# OSSC_HDMI_Audio_v1_5_A3.net
KiCad netlist of a schematic drawn in EAGLE
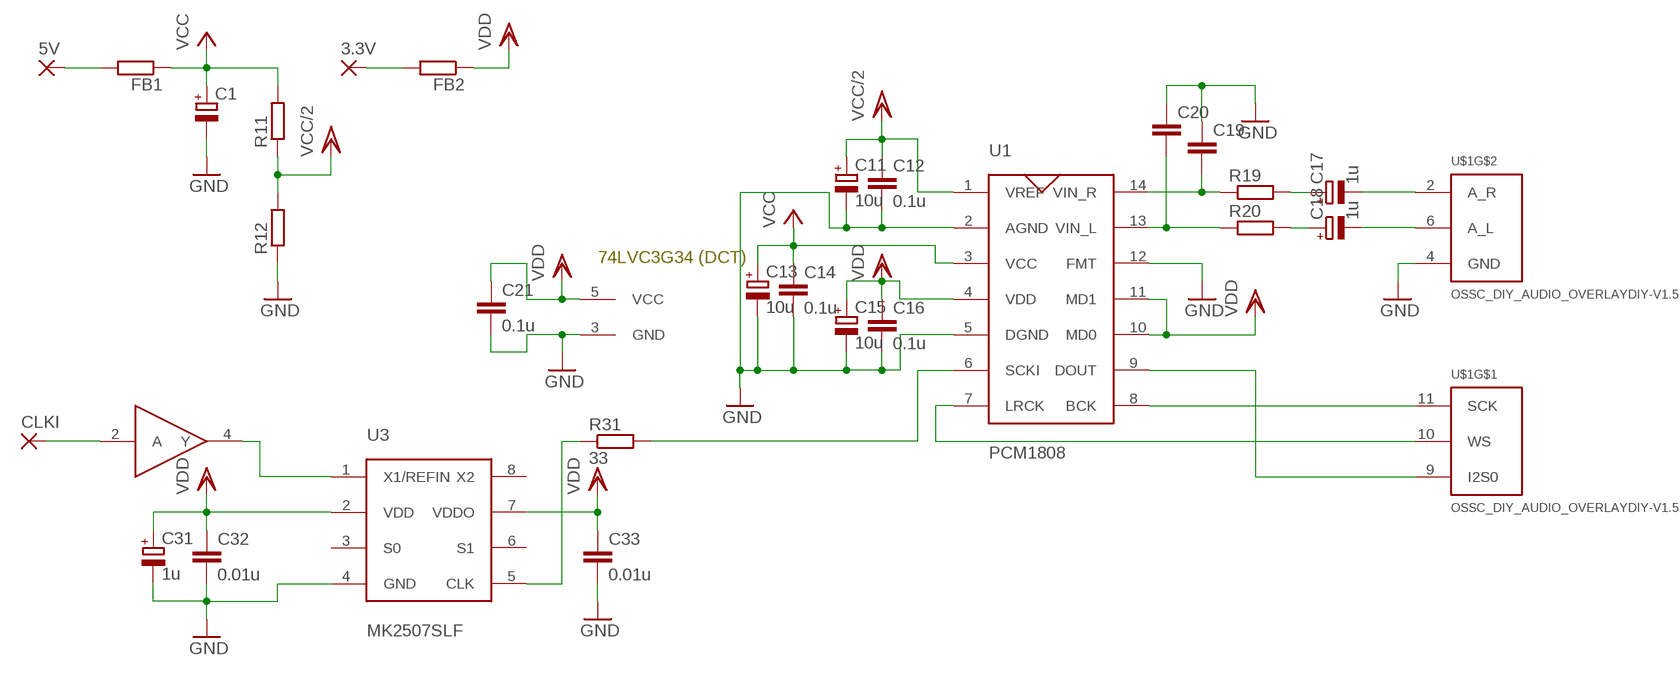
[diagram p0: schematic, sheet 1]

(export (version "E")
  (design (tool "Eeschema 10.0.6"))
  (components
    (comp (ref "3.3V")
      (value "SMD2")
      (footprint "eagle-import:SMD1,27-2,54")
      (libsource (lib "eagle-import") (part "SMD2"))
    )
    (comp (ref "5V")
      (value "SMD2")
      (footprint "eagle-import:SMD1,27-2,54")
      (libsource (lib "eagle-import") (part "SMD2"))
    )
    (comp (ref "C1")
      (value "CPOL-EUSMCC")
      (footprint "eagle-import:SMC_C")
      (libsource (lib "eagle-import") (part "CPOL-EUSMCC"))
    )
    (comp (ref "C11")
      (value "10u")
      (footprint "eagle-import:SMC_A")
      (libsource (lib "eagle-import") (part "CPOL-EUSMCA"))
    )
    (comp (ref "C12")
      (value "0.1u")
      (footprint "eagle-import:C0603")
      (libsource (lib "eagle-import") (part "C-EUC0603"))
    )
    (comp (ref "C13")
      (value "10u")
      (footprint "eagle-import:SMC_A")
      (libsource (lib "eagle-import") (part "CPOL-EUSMCA"))
    )
    (comp (ref "C14")
      (value "0.1u")
      (footprint "eagle-import:C0603")
      (libsource (lib "eagle-import") (part "C-EUC0603"))
    )
    (comp (ref "C15")
      (value "10u")
      (footprint "eagle-import:SMC_A")
      (libsource (lib "eagle-import") (part "CPOL-EUSMCA"))
    )
    (comp (ref "C16")
      (value "0.1u")
      (footprint "eagle-import:C0603")
      (libsource (lib "eagle-import") (part "C-EUC0603"))
    )
    (comp (ref "C17")
      (value "1u")
      (footprint "eagle-import:SMC_A")
      (libsource (lib "eagle-import") (part "CPOL-EUSMCA"))
    )
    (comp (ref "C18")
      (value "1u")
      (footprint "eagle-import:SMC_A")
      (libsource (lib "eagle-import") (part "CPOL-EUSMCA"))
    )
    (comp (ref "C19")
      (value "C-EUC0603")
      (footprint "eagle-import:C0603")
      (libsource (lib "eagle-import") (part "C-EUC0603"))
    )
    (comp (ref "C20")
      (value "C-EUC0603")
      (footprint "eagle-import:C0603")
      (libsource (lib "eagle-import") (part "C-EUC0603"))
    )
    (comp (ref "C21")
      (value "0.1u")
      (footprint "eagle-import:C0603")
      (libsource (lib "eagle-import") (part "C-EUC0603"))
    )
    (comp (ref "C31")
      (value "1u")
      (footprint "eagle-import:SMC_A")
      (libsource (lib "eagle-import") (part "CPOL-EUSMCA"))
    )
    (comp (ref "C32")
      (value "0.01u")
      (footprint "eagle-import:C0603")
      (libsource (lib "eagle-import") (part "C-EUC0603"))
    )
    (comp (ref "C33")
      (value "0.01u")
      (footprint "eagle-import:C0603")
      (libsource (lib "eagle-import") (part "C-EUC0603"))
    )
    (comp (ref "CLKI")
      (value "SMD2")
      (footprint "eagle-import:SMD1,27-2,54")
      (libsource (lib "eagle-import") (part "SMD2"))
    )
    (comp (ref "FB1")
      (value "R-EU_R0603")
      (footprint "eagle-import:R0603")
      (libsource (lib "eagle-import") (part "R-EU_R0603"))
    )
    (comp (ref "FB2")
      (value "R-EU_R0603")
      (footprint "eagle-import:R0603")
      (libsource (lib "eagle-import") (part "R-EU_R0603"))
    )
    (comp (ref "R11")
      (value "R-EU_R0603")
      (footprint "eagle-import:R0603")
      (libsource (lib "eagle-import") (part "R-EU_R0603"))
    )
    (comp (ref "R12")
      (value "R-EU_R0603")
      (footprint "eagle-import:R0603")
      (libsource (lib "eagle-import") (part "R-EU_R0603"))
    )
    (comp (ref "R19")
      (value "R-EU_R0603")
      (footprint "eagle-import:R0603")
      (libsource (lib "eagle-import") (part "R-EU_R0603"))
    )
    (comp (ref "R20")
      (value "R-EU_R0603")
      (footprint "eagle-import:R0603")
      (libsource (lib "eagle-import") (part "R-EU_R0603"))
    )
    (comp (ref "R31")
      (value "33")
      (footprint "eagle-import:R0603")
      (libsource (lib "eagle-import") (part "R-EU_R0603"))
    )
    (comp (ref "U$1")
      (value "OSSC_DIY_AUDIO_OVERLAYDIY-V1.5")
      (footprint "eagle-import:OSSC_OVERLAY_V1.5")
      (libsource (lib "eagle-import") (part "OSSC_DIY_AUDIO_OVERLAYDIY-V1.5"))
    )
    (comp (ref "U1")
      (value "PCM1808")
      (footprint "eagle-import:PCM1808")
      (libsource (lib "eagle-import") (part "PCM1808"))
    )
    (comp (ref "U2")
      (value "74LVC1G34")
      (footprint "eagle-import:74LVC1G34DCK")
      (libsource (lib "eagle-import") (part "74LVC1G34"))
    )
    (comp (ref "U3")
      (value "MK2507SLF")
      (footprint "eagle-import:SOIC8")
      (libsource (lib "eagle-import") (part "MK2507SLF"))
    )
  )
  (nets
    (net (code "1") (name "GND") (class "Default")
      (node (ref "C1") (pin "-") (pinfunction "-_-") (pintype "passive"))
      (node (ref "C11") (pin "-") (pinfunction "-_-") (pintype "passive"))
      (node (ref "C12") (pin "2") (pinfunction "2_2") (pintype "passive"))
      (node (ref "C13") (pin "-") (pinfunction "-_-") (pintype "passive"))
      (node (ref "C14") (pin "2") (pinfunction "2_2") (pintype "passive"))
      (node (ref "C15") (pin "-") (pinfunction "-_-") (pintype "passive"))
      (node (ref "C16") (pin "2") (pinfunction "2_2") (pintype "passive"))
      (node (ref "C19") (pin "1") (pinfunction "1_1") (pintype "passive"))
      (node (ref "C20") (pin "1") (pinfunction "1_1") (pintype "passive"))
      (node (ref "C21") (pin "2") (pinfunction "2_2") (pintype "passive"))
      (node (ref "C31") (pin "-") (pinfunction "-_-") (pintype "passive"))
      (node (ref "C32") (pin "2") (pinfunction "2_2") (pintype "passive"))
      (node (ref "C33") (pin "2") (pinfunction "2_2") (pintype "passive"))
      (node (ref "R12") (pin "1") (pinfunction "1_1") (pintype "passive"))
      (node (ref "U$1") (pin "4") (pinfunction "GND_4") (pintype "bidirectional"))
      (node (ref "U1") (pin "12") (pinfunction "FMT_12") (pintype "bidirectional"))
      (node (ref "U1") (pin "2") (pinfunction "AGND_2") (pintype "bidirectional"))
      (node (ref "U1") (pin "5") (pinfunction "DGND_5") (pintype "bidirectional"))
      (node (ref "U2") (pin "3") (pinfunction "GND_3") (pintype "bidirectional"))
      (node (ref "U3") (pin "4") (pinfunction "GND_4") (pintype "bidirectional"))
    )
    (net (code "2") (name "Net-(3.3V-P)") (class "Default")
      (node (ref "3.3V") (pin "1") (pinfunction "P_1") (pintype "passive"))
      (node (ref "FB2") (pin "2") (pinfunction "2_2") (pintype "passive"))
    )
    (net (code "3") (name "Net-(5V-P)") (class "Default")
      (node (ref "5V") (pin "1") (pinfunction "P_1") (pintype "passive"))
      (node (ref "FB1") (pin "2") (pinfunction "2_2") (pintype "passive"))
    )
    (net (code "4") (name "Net-(C17-Pad+)") (class "Default")
      (node (ref "C17") (pin "+") (pinfunction "+_+") (pintype "passive"))
      (node (ref "R19") (pin "2") (pinfunction "2_2") (pintype "passive"))
    )
    (net (code "5") (name "Net-(C18-Pad+)") (class "Default")
      (node (ref "C18") (pin "+") (pinfunction "+_+") (pintype "passive"))
      (node (ref "R20") (pin "2") (pinfunction "2_2") (pintype "passive"))
    )
    (net (code "6") (name "Net-(CLKI-P)") (class "Default")
      (node (ref "CLKI") (pin "1") (pinfunction "P_1") (pintype "passive"))
      (node (ref "U2") (pin "2") (pinfunction "A_2") (pintype "bidirectional"))
    )
    (net (code "7") (name "Net-(U$1A-I2S0)") (class "Default")
      (node (ref "U$1") (pin "9") (pinfunction "I2S0_9") (pintype "bidirectional"))
      (node (ref "U1") (pin "9") (pinfunction "DOUT_9") (pintype "bidirectional"))
    )
    (net (code "8") (name "Net-(U$1A-SCK)") (class "Default")
      (node (ref "U$1") (pin "11") (pinfunction "SCK_11") (pintype "bidirectional"))
      (node (ref "U1") (pin "8") (pinfunction "BCK_8") (pintype "bidirectional"))
    )
    (net (code "9") (name "Net-(U$1A-WS)") (class "Default")
      (node (ref "U$1") (pin "10") (pinfunction "WS_10") (pintype "bidirectional"))
      (node (ref "U1") (pin "7") (pinfunction "LRCK_7") (pintype "bidirectional"))
    )
    (net (code "10") (name "Net-(U$1B-A_L)") (class "Default")
      (node (ref "C18") (pin "-") (pinfunction "-_-") (pintype "passive"))
      (node (ref "U$1") (pin "6") (pinfunction "A_L_6") (pintype "bidirectional"))
    )
    (net (code "11") (name "Net-(U$1B-A_R)") (class "Default")
      (node (ref "C17") (pin "-") (pinfunction "-_-") (pintype "passive"))
      (node (ref "U$1") (pin "2") (pinfunction "A_R_2") (pintype "bidirectional"))
    )
    (net (code "12") (name "Net-(U1-SCKI)") (class "Default")
      (node (ref "R31") (pin "2") (pinfunction "2_2") (pintype "passive"))
      (node (ref "U1") (pin "6") (pinfunction "SCKI_6") (pintype "bidirectional"))
    )
    (net (code "13") (name "Net-(U1-VIN_L)") (class "Default")
      (node (ref "C20") (pin "2") (pinfunction "2_2") (pintype "passive"))
      (node (ref "R20") (pin "1") (pinfunction "1_1") (pintype "passive"))
      (node (ref "U1") (pin "13") (pinfunction "VIN_L_13") (pintype "bidirectional"))
    )
    (net (code "14") (name "Net-(U1-VIN_R)") (class "Default")
      (node (ref "C19") (pin "2") (pinfunction "2_2") (pintype "passive"))
      (node (ref "R19") (pin "1") (pinfunction "1_1") (pintype "passive"))
      (node (ref "U1") (pin "14") (pinfunction "VIN_R_14") (pintype "bidirectional"))
    )
    (net (code "15") (name "Net-(U2A-Y)") (class "Default")
      (node (ref "U2") (pin "4") (pinfunction "Y_4") (pintype "bidirectional"))
      (node (ref "U3") (pin "1") (pinfunction "X1/REFIN_1") (pintype "bidirectional"))
    )
    (net (code "16") (name "Net-(U3-CLK)") (class "Default")
      (node (ref "R31") (pin "1") (pinfunction "1_1") (pintype "passive"))
      (node (ref "U3") (pin "5") (pinfunction "CLK_5") (pintype "bidirectional"))
    )
    (net (code "17") (name "VCC") (class "Default")
      (node (ref "C1") (pin "+") (pinfunction "+_+") (pintype "passive"))
      (node (ref "C13") (pin "+") (pinfunction "+_+") (pintype "passive"))
      (node (ref "C14") (pin "1") (pinfunction "1_1") (pintype "passive"))
      (node (ref "FB1") (pin "1") (pinfunction "1_1") (pintype "passive"))
      (node (ref "R11") (pin "2") (pinfunction "2_2") (pintype "passive"))
      (node (ref "U1") (pin "3") (pinfunction "VCC_3") (pintype "bidirectional"))
    )
    (net (code "18") (name "VCC{slash}2") (class "Default")
      (node (ref "C11") (pin "+") (pinfunction "+_+") (pintype "passive"))
      (node (ref "C12") (pin "1") (pinfunction "1_1") (pintype "passive"))
      (node (ref "R11") (pin "1") (pinfunction "1_1") (pintype "passive"))
      (node (ref "R12") (pin "2") (pinfunction "2_2") (pintype "passive"))
      (node (ref "U1") (pin "1") (pinfunction "VREF_1") (pintype "bidirectional"))
    )
    (net (code "19") (name "VDD") (class "Default")
      (node (ref "C15") (pin "+") (pinfunction "+_+") (pintype "passive"))
      (node (ref "C16") (pin "1") (pinfunction "1_1") (pintype "passive"))
      (node (ref "C21") (pin "1") (pinfunction "1_1") (pintype "passive"))
      (node (ref "C31") (pin "+") (pinfunction "+_+") (pintype "passive"))
      (node (ref "C32") (pin "1") (pinfunction "1_1") (pintype "passive"))
      (node (ref "C33") (pin "1") (pinfunction "1_1") (pintype "passive"))
      (node (ref "FB2") (pin "1") (pinfunction "1_1") (pintype "passive"))
      (node (ref "U1") (pin "10") (pinfunction "MD0_10") (pintype "bidirectional"))
      (node (ref "U1") (pin "11") (pinfunction "MD1_11") (pintype "bidirectional"))
      (node (ref "U1") (pin "4") (pinfunction "VDD_4") (pintype "bidirectional"))
      (node (ref "U2") (pin "5") (pinfunction "VCC_5") (pintype "bidirectional"))
      (node (ref "U3") (pin "2") (pinfunction "VDD_2") (pintype "bidirectional"))
      (node (ref "U3") (pin "7") (pinfunction "VDDO_7") (pintype "bidirectional"))
    )
    (net (code "20") (name "unconnected-(U3-S0-Pad3)") (class "Default")
      (node (ref "U3") (pin "3") (pinfunction "S0_3") (pintype "bidirectional"))
    )
    (net (code "21") (name "unconnected-(U3-S1-Pad6)") (class "Default")
      (node (ref "U3") (pin "6") (pinfunction "S1_6") (pintype "bidirectional"))
    )
    (net (code "22") (name "unconnected-(U3-X2-Pad8)") (class "Default")
      (node (ref "U3") (pin "8") (pinfunction "X2_8") (pintype "bidirectional"))
    )
  )
)
